# Programmer.net
KiCad netlist of a schematic drawn in Altium Designer
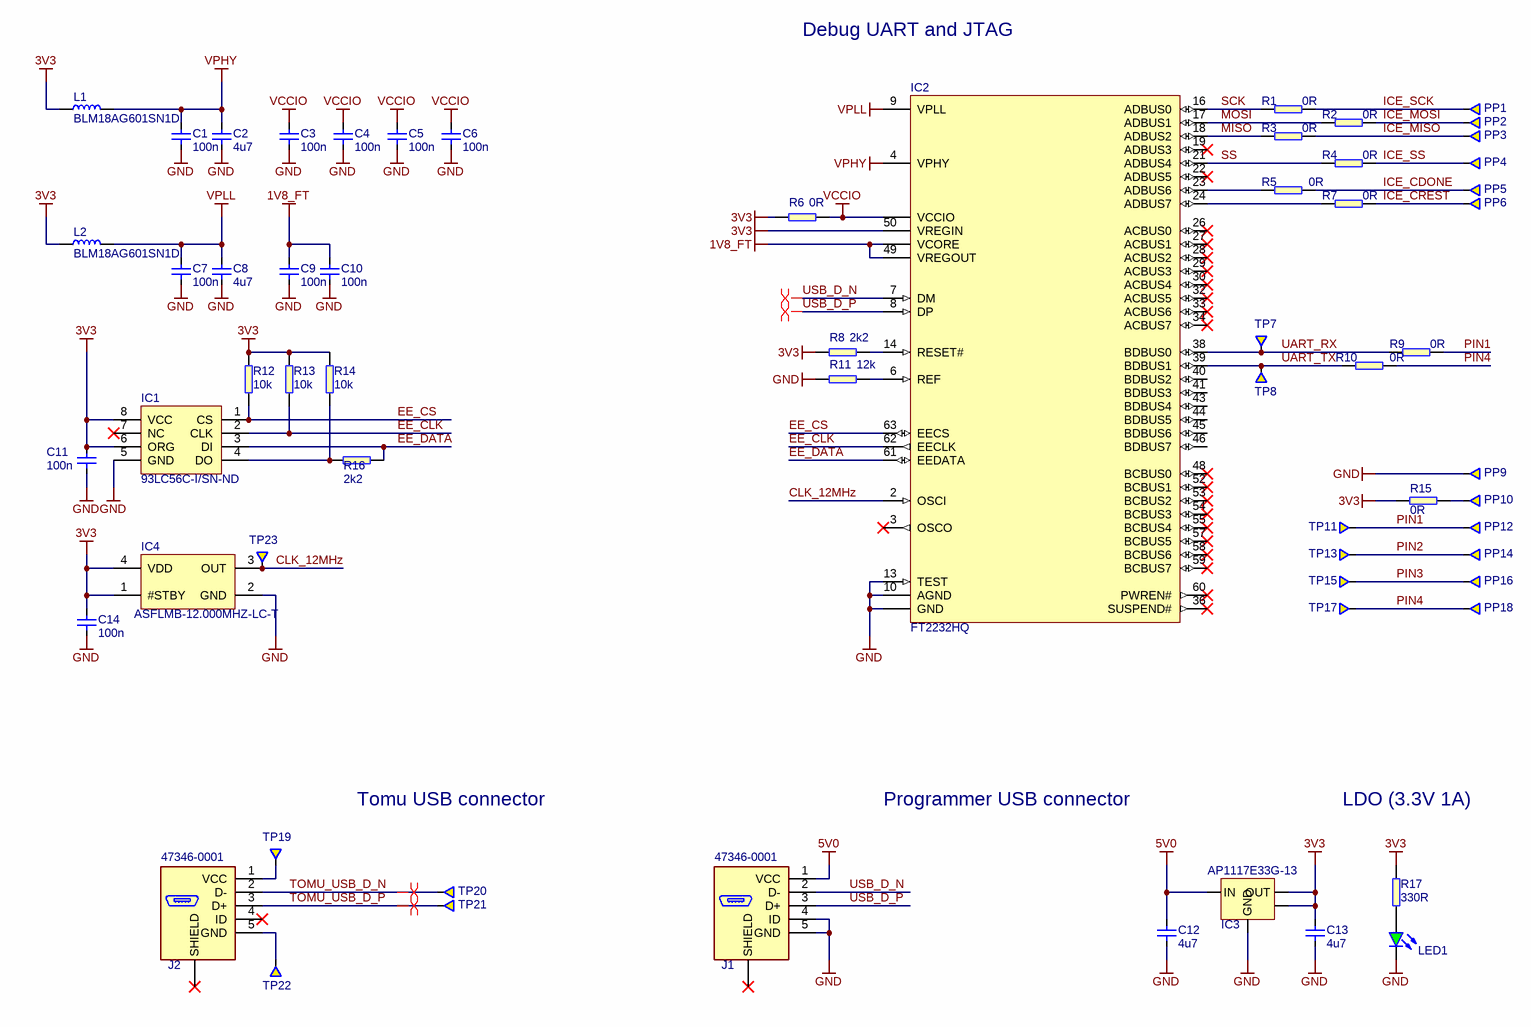
[diagram p0: Programmer.SchDoc]

(export (version "E")
  (design (tool "Eeschema 10.0.6"))
  (components
    (comp (ref "C1")
      (value "100n")
      (footprint "0402")
      (description "MLCC SMT Capacitor 100nF 0402")
      (fields (field (name "PARTNUMBER") "C_100n_0402") (field (name "MANUFACTURER") "AVX"))
      (libsource (lib "Tomu-ICE-Programmer-Rev.1.0") (part "C_100n_0402"))
    )
    (comp (ref "C2")
      (value "4u7")
      (footprint "0402")
      (description "MLCC SMT Capacitor 100nF 0402")
      (fields (field (name "PARTNUMBER") "C_4u7_0402") (field (name "MANUFACTURER") "TDK"))
      (libsource (lib "Tomu-ICE-Programmer-Rev.1.0") (part "C_4u7_0402"))
    )
    (comp (ref "C3")
      (value "100n")
      (footprint "0402")
      (description "MLCC SMT Capacitor 100nF 0402")
      (fields (field (name "PARTNUMBER") "C_100n_0402") (field (name "MANUFACTURER") "AVX"))
      (libsource (lib "Tomu-ICE-Programmer-Rev.1.0") (part "C_100n_0402"))
    )
    (comp (ref "C4")
      (value "100n")
      (footprint "0402")
      (description "MLCC SMT Capacitor 100nF 0402")
      (fields (field (name "PARTNUMBER") "C_100n_0402") (field (name "MANUFACTURER") "AVX"))
      (libsource (lib "Tomu-ICE-Programmer-Rev.1.0") (part "C_100n_0402"))
    )
    (comp (ref "C5")
      (value "100n")
      (footprint "0402")
      (description "MLCC SMT Capacitor 100nF 0402")
      (fields (field (name "PARTNUMBER") "C_100n_0402") (field (name "MANUFACTURER") "AVX"))
      (libsource (lib "Tomu-ICE-Programmer-Rev.1.0") (part "C_100n_0402"))
    )
    (comp (ref "C6")
      (value "100n")
      (footprint "0402")
      (description "MLCC SMT Capacitor 100nF 0402")
      (fields (field (name "PARTNUMBER") "C_100n_0402") (field (name "MANUFACTURER") "AVX"))
      (libsource (lib "Tomu-ICE-Programmer-Rev.1.0") (part "C_100n_0402"))
    )
    (comp (ref "C7")
      (value "100n")
      (footprint "0402")
      (description "MLCC SMT Capacitor 100nF 0402")
      (fields (field (name "PARTNUMBER") "C_100n_0402") (field (name "MANUFACTURER") "AVX"))
      (libsource (lib "Tomu-ICE-Programmer-Rev.1.0") (part "C_100n_0402"))
    )
    (comp (ref "C8")
      (value "4u7")
      (footprint "0402")
      (description "MLCC SMT Capacitor 100nF 0402")
      (fields (field (name "PARTNUMBER") "C_4u7_0402") (field (name "MANUFACTURER") "TDK"))
      (libsource (lib "Tomu-ICE-Programmer-Rev.1.0") (part "C_4u7_0402"))
    )
    (comp (ref "C9")
      (value "100n")
      (footprint "0402")
      (description "MLCC SMT Capacitor 100nF 0402")
      (fields (field (name "PARTNUMBER") "C_100n_0402") (field (name "MANUFACTURER") "AVX"))
      (libsource (lib "Tomu-ICE-Programmer-Rev.1.0") (part "C_100n_0402"))
    )
    (comp (ref "C10")
      (value "100n")
      (footprint "0402")
      (description "MLCC SMT Capacitor 100nF 0402")
      (fields (field (name "PARTNUMBER") "C_100n_0402") (field (name "MANUFACTURER") "AVX"))
      (libsource (lib "Tomu-ICE-Programmer-Rev.1.0") (part "C_100n_0402"))
    )
    (comp (ref "C11")
      (value "100n")
      (footprint "0402")
      (description "MLCC SMT Capacitor 100nF 0402")
      (fields (field (name "PARTNUMBER") "C_100n_0402") (field (name "MANUFACTURER") "AVX"))
      (libsource (lib "Tomu-ICE-Programmer-Rev.1.0") (part "C_100n_0402"))
    )
    (comp (ref "C12")
      (value "4u7")
      (footprint "0402")
      (description "MLCC SMT Capacitor 100nF 0402")
      (fields (field (name "PARTNUMBER") "C_4u7_0402") (field (name "MANUFACTURER") "TDK"))
      (libsource (lib "Tomu-ICE-Programmer-Rev.1.0") (part "C_4u7_0402"))
    )
    (comp (ref "C13")
      (value "4u7")
      (footprint "0402")
      (description "MLCC SMT Capacitor 100nF 0402")
      (fields (field (name "PARTNUMBER") "C_4u7_0402") (field (name "MANUFACTURER") "TDK"))
      (libsource (lib "Tomu-ICE-Programmer-Rev.1.0") (part "C_4u7_0402"))
    )
    (comp (ref "C14")
      (value "100n")
      (footprint "0402")
      (description "MLCC SMT Capacitor 100nF 0402")
      (fields (field (name "PARTNUMBER") "C_100n_0402") (field (name "MANUFACTURER") "AVX"))
      (libsource (lib "Tomu-ICE-Programmer-Rev.1.0") (part "C_100n_0402"))
    )
    (comp (ref "IC1")
      (value "93LC56C-I/SN-ND")
      (footprint "SOIC-8")
      (description "EEPROM SERIAL 1K, SMD, 93C46, SOIC8")
      (fields (field (name "PARTNUMBER") "93LC56C") (field (name "MANUFACTURER") "Microchip Technology"))
      (libsource (lib "Tomu-ICE-Programmer-Rev.1.0") (part "93LC56C"))
    )
    (comp (ref "IC2")
      (value "FT2232HQ")
      (footprint "FT2232HQ")
      (description "Dual USB-UART/FIFO")
      (fields (field (name "MANUFACTURER") "FTDI") (field (name "PARTNUMBER") "FT2232HQ"))
      (libsource (lib "Tomu-ICE-Programmer-Rev.1.0") (part "FT2232HL"))
    )
    (comp (ref "IC3")
      (value "AP1117E33G-13")
      (footprint "SOT223")
      (description "IC, LDO, REG, 3.3V, SOT223")
      (fields (field (name "MANUFACTURER") "DIODES INC."))
      (libsource (lib "Tomu-ICE-Programmer-Rev.1.0") (part "xx1117"))
    )
    (comp (ref "IC4")
      (value "ASFLMB-12.000MHZ-LC-T")
      (footprint "ASFLMB")
      (description "MEMS Oscillator, Ultra-miniature, 12 MHz, SMD, 5mm x 3.2mm, 50 ppm, 3.3 V")
      (fields (field (name "MANUFACTURER") "Abracon LLC"))
      (libsource (lib "Tomu-ICE-Programmer-Rev.1.0") (part "ASFLMB"))
    )
    (comp (ref "J1")
      (value "Molex 47346-0001")
      (footprint "CON-Molex-047346-0001")
      (description "USB - micro B Receptacle Connector 5 Position Surface Mount, Right Angle, Horizontal")
      (fields
        (field (name "PARTNUMBER") "CON-Molex-47346-0001")
        (field (name "MANUFACTURER") "Molex")
        (field (name "PARTSYMBOL") "47346-0001")
      )
      (libsource (lib "Tomu-ICE-Programmer-Rev.1.0") (part "Micro USB B"))
    )
    (comp (ref "J2")
      (value "Molex 47346-0001")
      (footprint "CON-Molex-047346-0001")
      (description "USB - micro B Receptacle Connector 5 Position Surface Mount, Right Angle, Horizontal")
      (fields
        (field (name "PARTNUMBER") "CON-Molex-47346-0001")
        (field (name "MANUFACTURER") "Molex")
        (field (name "PARTSYMBOL") "47346-0001")
      )
      (libsource (lib "Tomu-ICE-Programmer-Rev.1.0") (part "Micro USB B"))
    )
    (comp (ref "L1")
      (value "BLM18AG601SN1D")
      (footprint "0603")
      (description "Ferrite Bead, 600 ohm, 0603 [1608 Metric], BLM18A Series, 500 mA, 0.38 ohm, ? 25%")
      (fields (field (name "MANUFACTURER") "MURATA"))
      (libsource (lib "Tomu-ICE-Programmer-Rev.1.0") (part "Inductor SMT"))
    )
    (comp (ref "L2")
      (value "BLM18AG601SN1D")
      (footprint "0603")
      (description "Ferrite Bead, 600 ohm, 0603 [1608 Metric], BLM18A Series, 500 mA, 0.38 ohm, ? 25%")
      (fields (field (name "MANUFACTURER") "MURATA"))
      (libsource (lib "Tomu-ICE-Programmer-Rev.1.0") (part "Inductor SMT"))
    )
    (comp (ref "LED1")
      (value "KPT-1608SGC")
      (footprint "LED0603")
      (description "LED Green 0603 case")
      (fields (field (name "PARTNUMBER") "LED_G") (field (name "MANUFACTURER") "KINGBRIGHT"))
      (libsource (lib "Tomu-ICE-Programmer-Rev.1.0") (part "LED"))
    )
    (comp (ref "PP1")
      (value "~")
      (footprint "TP-R-1.5-THT")
      (description "Testpad, round, 1.8mm")
      (fields (field (name "PARTNUMBER") "P70-2300045R") (field (name "MANUFACTURER") "Harwin"))
      (libsource (lib "Tomu-ICE-Programmer-Rev.1.0") (part "Testpad_pin"))
    )
    (comp (ref "PP2")
      (value "~")
      (footprint "TP-R-1.5-THT")
      (description "Testpad, round, 1.8mm")
      (fields (field (name "PARTNUMBER") "P70-2300045R") (field (name "MANUFACTURER") "Harwin"))
      (libsource (lib "Tomu-ICE-Programmer-Rev.1.0") (part "Testpad_pin"))
    )
    (comp (ref "PP3")
      (value "~")
      (footprint "TP-R-1.5-THT")
      (description "Testpad, round, 1.8mm")
      (fields (field (name "PARTNUMBER") "P70-2300045R") (field (name "MANUFACTURER") "Harwin"))
      (libsource (lib "Tomu-ICE-Programmer-Rev.1.0") (part "Testpad_pin"))
    )
    (comp (ref "PP4")
      (value "~")
      (footprint "TP-R-1.5-THT")
      (description "Testpad, round, 1.8mm")
      (fields (field (name "PARTNUMBER") "P70-2300045R") (field (name "MANUFACTURER") "Harwin"))
      (libsource (lib "Tomu-ICE-Programmer-Rev.1.0") (part "Testpad_pin"))
    )
    (comp (ref "PP5")
      (value "~")
      (footprint "TP-R-1.5-THT")
      (description "Testpad, round, 1.8mm")
      (fields (field (name "PARTNUMBER") "P70-2300045R") (field (name "MANUFACTURER") "Harwin"))
      (libsource (lib "Tomu-ICE-Programmer-Rev.1.0") (part "Testpad_pin"))
    )
    (comp (ref "PP6")
      (value "~")
      (footprint "TP-R-1.5-THT")
      (description "Testpad, round, 1.8mm")
      (fields (field (name "PARTNUMBER") "P70-2300045R") (field (name "MANUFACTURER") "Harwin"))
      (libsource (lib "Tomu-ICE-Programmer-Rev.1.0") (part "Testpad_pin"))
    )
    (comp (ref "PP9")
      (value "~")
      (footprint "TP-R-1.5-THT")
      (description "Testpad, round, 1.8mm")
      (fields (field (name "PARTNUMBER") "P70-2300045R") (field (name "MANUFACTURER") "Harwin"))
      (libsource (lib "Tomu-ICE-Programmer-Rev.1.0") (part "Testpad_pin"))
    )
    (comp (ref "PP10")
      (value "~")
      (footprint "TP-R-1.5-THT")
      (description "Testpad, round, 1.8mm")
      (fields (field (name "PARTNUMBER") "P70-2300045R") (field (name "MANUFACTURER") "Harwin"))
      (libsource (lib "Tomu-ICE-Programmer-Rev.1.0") (part "Testpad_pin"))
    )
    (comp (ref "PP12")
      (value "~")
      (footprint "TP-R-1.5-THT")
      (description "Testpad, round, 1.8mm")
      (fields (field (name "PARTNUMBER") "P70-2300045R") (field (name "MANUFACTURER") "Harwin"))
      (libsource (lib "Tomu-ICE-Programmer-Rev.1.0") (part "Testpad_pin"))
    )
    (comp (ref "PP14")
      (value "~")
      (footprint "TP-R-1.5-THT")
      (description "Testpad, round, 1.8mm")
      (fields (field (name "PARTNUMBER") "P70-2300045R") (field (name "MANUFACTURER") "Harwin"))
      (libsource (lib "Tomu-ICE-Programmer-Rev.1.0") (part "Testpad_pin"))
    )
    (comp (ref "PP16")
      (value "~")
      (footprint "TP-R-1.5-THT")
      (description "Testpad, round, 1.8mm")
      (fields (field (name "PARTNUMBER") "P70-2300045R") (field (name "MANUFACTURER") "Harwin"))
      (libsource (lib "Tomu-ICE-Programmer-Rev.1.0") (part "Testpad_pin"))
    )
    (comp (ref "PP18")
      (value "~")
      (footprint "TP-R-1.5-THT")
      (description "Testpad, round, 1.8mm")
      (fields (field (name "PARTNUMBER") "P70-2300045R") (field (name "MANUFACTURER") "Harwin"))
      (libsource (lib "Tomu-ICE-Programmer-Rev.1.0") (part "Testpad_pin"))
    )
    (comp (ref "R1")
      (value "0R")
      (footprint "0402")
      (description "SMT Resistor 0402")
      (fields (field (name "PARTNUMBER") "R_0R_0402") (field (name "MANUFACTURER") "Vishay"))
      (libsource (lib "Tomu-ICE-Programmer-Rev.1.0") (part "R_0R_0402"))
    )
    (comp (ref "R2")
      (value "0R")
      (footprint "0402")
      (description "SMT Resistor 0402")
      (fields (field (name "PARTNUMBER") "R_0R_0402") (field (name "MANUFACTURER") "Vishay"))
      (libsource (lib "Tomu-ICE-Programmer-Rev.1.0") (part "R_0R_0402"))
    )
    (comp (ref "R3")
      (value "0R")
      (footprint "0402")
      (description "SMT Resistor 0402")
      (fields (field (name "PARTNUMBER") "R_0R_0402") (field (name "MANUFACTURER") "Vishay"))
      (libsource (lib "Tomu-ICE-Programmer-Rev.1.0") (part "R_0R_0402"))
    )
    (comp (ref "R4")
      (value "0R")
      (footprint "0402")
      (description "SMT Resistor 0402")
      (fields (field (name "PARTNUMBER") "R_0R_0402") (field (name "MANUFACTURER") "Vishay"))
      (libsource (lib "Tomu-ICE-Programmer-Rev.1.0") (part "R_0R_0402"))
    )
    (comp (ref "R5")
      (value "0R")
      (footprint "0402")
      (description "SMT Resistor 0402")
      (fields (field (name "PARTNUMBER") "R_0R_0402") (field (name "MANUFACTURER") "Vishay"))
      (libsource (lib "Tomu-ICE-Programmer-Rev.1.0") (part "R_0R_0402"))
    )
    (comp (ref "R6")
      (value "0R")
      (footprint "0402")
      (description "SMT Resistor 0402")
      (fields (field (name "PARTNUMBER") "R_0R_0402") (field (name "MANUFACTURER") "Vishay"))
      (libsource (lib "Tomu-ICE-Programmer-Rev.1.0") (part "R_0R_0402"))
    )
    (comp (ref "R7")
      (value "0R")
      (footprint "0402")
      (description "SMT Resistor 0402")
      (fields (field (name "PARTNUMBER") "R_0R_0402") (field (name "MANUFACTURER") "Vishay"))
      (libsource (lib "Tomu-ICE-Programmer-Rev.1.0") (part "R_0R_0402"))
    )
    (comp (ref "R8")
      (value "2k2")
      (footprint "0402")
      (description "SMT Resistor 0402")
      (fields (field (name "PARTNUMBER") "R_2k2_0402") (field (name "MANUFACTURER") "Vishay"))
      (libsource (lib "Tomu-ICE-Programmer-Rev.1.0") (part "R_2k2_0402"))
    )
    (comp (ref "R9")
      (value "0R")
      (footprint "0402")
      (description "SMT Resistor 0402")
      (fields (field (name "PARTNUMBER") "R_0R_0402") (field (name "MANUFACTURER") "Vishay"))
      (libsource (lib "Tomu-ICE-Programmer-Rev.1.0") (part "R_0R_0402"))
    )
    (comp (ref "R10")
      (value "0R")
      (footprint "0402")
      (description "SMT Resistor 0402")
      (fields (field (name "PARTNUMBER") "R_0R_0402") (field (name "MANUFACTURER") "Vishay"))
      (libsource (lib "Tomu-ICE-Programmer-Rev.1.0") (part "R_0R_0402"))
    )
    (comp (ref "R11")
      (value "12k")
      (footprint "0402")
      (description "SMT Resistor 0402")
      (fields (field (name "PARTNUMBER") "R_12k_0402") (field (name "MANUFACTURER") "Multicomp"))
      (libsource (lib "Tomu-ICE-Programmer-Rev.1.0") (part "R_12k_0402"))
    )
    (comp (ref "R12")
      (value "10k")
      (footprint "0402")
      (description "SMT Resistor 0402")
      (fields (field (name "PARTNUMBER") "R_10k_0402") (field (name "MANUFACTURER") "Vishay"))
      (libsource (lib "Tomu-ICE-Programmer-Rev.1.0") (part "R_10k_0402"))
    )
    (comp (ref "R13")
      (value "10k")
      (footprint "0402")
      (description "SMT Resistor 0402")
      (fields (field (name "PARTNUMBER") "R_10k_0402") (field (name "MANUFACTURER") "Vishay"))
      (libsource (lib "Tomu-ICE-Programmer-Rev.1.0") (part "R_10k_0402"))
    )
    (comp (ref "R14")
      (value "10k")
      (footprint "0402")
      (description "SMT Resistor 0402")
      (fields (field (name "PARTNUMBER") "R_10k_0402") (field (name "MANUFACTURER") "Vishay"))
      (libsource (lib "Tomu-ICE-Programmer-Rev.1.0") (part "R_10k_0402"))
    )
    (comp (ref "R15")
      (value "0R")
      (footprint "0402")
      (description "SMT Resistor 0402")
      (fields (field (name "PARTNUMBER") "R_0R_0402") (field (name "MANUFACTURER") "Vishay"))
      (libsource (lib "Tomu-ICE-Programmer-Rev.1.0") (part "R_0R_0402"))
    )
    (comp (ref "R16")
      (value "2k2")
      (footprint "0402")
      (description "SMT Resistor 0402")
      (fields (field (name "PARTNUMBER") "R_2k2_0402") (field (name "MANUFACTURER") "Vishay"))
      (libsource (lib "Tomu-ICE-Programmer-Rev.1.0") (part "R_2k2_0402"))
    )
    (comp (ref "R17")
      (value "330R")
      (footprint "0402")
      (description "SMT Resistor 0402")
      (fields (field (name "PARTNUMBER") "R_330R_0402") (field (name "MANUFACTURER") "Multicomp"))
      (libsource (lib "Tomu-ICE-Programmer-Rev.1.0") (part "R_330R_0402"))
    )
    (comp (ref "TP7")
      (value "Testpad")
      (footprint "TP-R-1.5")
      (description "Testpad, round, 1.5mm")
      (fields (field (name "PARTNUMBER") "TP-R-1.5"))
      (libsource (lib "Tomu-ICE-Programmer-Rev.1.0") (part "Testpad"))
    )
    (comp (ref "TP8")
      (value "Testpad")
      (footprint "TP-R-1.5")
      (description "Testpad, round, 1.5mm")
      (fields (field (name "PARTNUMBER") "TP-R-1.5"))
      (libsource (lib "Tomu-ICE-Programmer-Rev.1.0") (part "Testpad"))
    )
    (comp (ref "TP11")
      (value "Testpad")
      (footprint "TP-R-1.5")
      (description "Testpad, round, 1.5mm")
      (fields (field (name "PARTNUMBER") "TP-R-1.5"))
      (libsource (lib "Tomu-ICE-Programmer-Rev.1.0") (part "Testpad"))
    )
    (comp (ref "TP13")
      (value "Testpad")
      (footprint "TP-R-1.5")
      (description "Testpad, round, 1.5mm")
      (fields (field (name "PARTNUMBER") "TP-R-1.5"))
      (libsource (lib "Tomu-ICE-Programmer-Rev.1.0") (part "Testpad"))
    )
    (comp (ref "TP15")
      (value "Testpad")
      (footprint "TP-R-1.5")
      (description "Testpad, round, 1.5mm")
      (fields (field (name "PARTNUMBER") "TP-R-1.5"))
      (libsource (lib "Tomu-ICE-Programmer-Rev.1.0") (part "Testpad"))
    )
    (comp (ref "TP17")
      (value "Testpad")
      (footprint "TP-R-1.5")
      (description "Testpad, round, 1.5mm")
      (fields (field (name "PARTNUMBER") "TP-R-1.5"))
      (libsource (lib "Tomu-ICE-Programmer-Rev.1.0") (part "Testpad"))
    )
    (comp (ref "TP19")
      (value "Testpad")
      (footprint "TP-R-1.5")
      (description "Testpad, round, 1.5mm")
      (fields (field (name "PARTNUMBER") "TP-R-1.5"))
      (libsource (lib "Tomu-ICE-Programmer-Rev.1.0") (part "Testpad"))
    )
    (comp (ref "TP20")
      (value "Testpad")
      (footprint "TP-R-1.5")
      (description "Testpad, round, 1.5mm")
      (fields (field (name "PARTNUMBER") "TP-R-1.5"))
      (libsource (lib "Tomu-ICE-Programmer-Rev.1.0") (part "Testpad"))
    )
    (comp (ref "TP21")
      (value "Testpad")
      (footprint "TP-R-1.5")
      (description "Testpad, round, 1.5mm")
      (fields (field (name "PARTNUMBER") "TP-R-1.5"))
      (libsource (lib "Tomu-ICE-Programmer-Rev.1.0") (part "Testpad"))
    )
    (comp (ref "TP22")
      (value "Testpad")
      (footprint "TP-R-1.5")
      (description "Testpad, round, 1.5mm")
      (fields (field (name "PARTNUMBER") "TP-R-1.5"))
      (libsource (lib "Tomu-ICE-Programmer-Rev.1.0") (part "Testpad"))
    )
    (comp (ref "TP23")
      (value "Testpad")
      (footprint "TP-R-1.5")
      (description "Testpad, round, 1.5mm")
      (fields (field (name "PARTNUMBER") "TP-R-1.5"))
      (libsource (lib "Tomu-ICE-Programmer-Rev.1.0") (part "Testpad"))
    )
  )
  (nets
    (net (code "1") (name "/CLK_12MHz") (class "Default")
      (node (ref "IC2") (pin "2") (pinfunction "OSCI_2") (pintype "input"))
      (node (ref "IC4") (pin "3") (pinfunction "OUT_3") (pintype "passive"))
      (node (ref "TP23") (pin "1") (pintype "passive"))
    )
    (net (code "2") (name "/EE_CLK") (class "Default")
      (node (ref "IC1") (pin "2") (pinfunction "CLK_2") (pintype "passive"))
      (node (ref "IC2") (pin "62") (pinfunction "EECLK_62") (pintype "output"))
      (node (ref "R13") (pin "1") (pintype "passive"))
    )
    (net (code "3") (name "/EE_CS") (class "Default")
      (node (ref "IC1") (pin "1") (pinfunction "CS_1") (pintype "passive"))
      (node (ref "IC2") (pin "63") (pinfunction "EECS_63") (pintype "bidirectional"))
      (node (ref "R12") (pin "1") (pintype "passive"))
    )
    (net (code "4") (name "/EE_DATA") (class "Default")
      (node (ref "IC1") (pin "3") (pinfunction "DI_3") (pintype "passive"))
      (node (ref "IC2") (pin "61") (pinfunction "EEDATA_61") (pintype "bidirectional"))
      (node (ref "R16") (pin "2") (pintype "passive"))
    )
    (net (code "5") (name "/ICE_CDONE") (class "Default")
      (node (ref "PP5") (pin "1") (pintype "passive"))
      (node (ref "R5") (pin "2") (pintype "passive"))
    )
    (net (code "6") (name "/ICE_CREST") (class "Default")
      (node (ref "PP6") (pin "1") (pintype "passive"))
      (node (ref "R7") (pin "2") (pintype "passive"))
    )
    (net (code "7") (name "/ICE_MISO") (class "Default")
      (node (ref "PP3") (pin "1") (pintype "passive"))
      (node (ref "R3") (pin "2") (pintype "passive"))
    )
    (net (code "8") (name "/ICE_MOSI") (class "Default")
      (node (ref "PP2") (pin "1") (pintype "passive"))
      (node (ref "R2") (pin "2") (pintype "passive"))
    )
    (net (code "9") (name "/ICE_SCK") (class "Default")
      (node (ref "PP1") (pin "1") (pintype "passive"))
      (node (ref "R1") (pin "2") (pintype "passive"))
    )
    (net (code "10") (name "/ICE_SS") (class "Default")
      (node (ref "PP4") (pin "1") (pintype "passive"))
      (node (ref "R4") (pin "2") (pintype "passive"))
    )
    (net (code "11") (name "/MISO") (class "Default")
      (node (ref "IC2") (pin "18") (pinfunction "ADBUS2_18") (pintype "bidirectional"))
      (node (ref "R3") (pin "1") (pintype "passive"))
    )
    (net (code "12") (name "/MOSI") (class "Default")
      (node (ref "IC2") (pin "17") (pinfunction "ADBUS1_17") (pintype "bidirectional"))
      (node (ref "R2") (pin "1") (pintype "passive"))
    )
    (net (code "13") (name "/PIN1") (class "Default")
      (node (ref "PP12") (pin "1") (pintype "passive"))
      (node (ref "R9") (pin "2") (pintype "passive"))
      (node (ref "TP11") (pin "1") (pintype "passive"))
    )
    (net (code "14") (name "/PIN2") (class "Default")
      (node (ref "PP14") (pin "1") (pintype "passive"))
      (node (ref "TP13") (pin "1") (pintype "passive"))
    )
    (net (code "15") (name "/PIN3") (class "Default")
      (node (ref "PP16") (pin "1") (pintype "passive"))
      (node (ref "TP15") (pin "1") (pintype "passive"))
    )
    (net (code "16") (name "/PIN4") (class "Default")
      (node (ref "PP18") (pin "1") (pintype "passive"))
      (node (ref "R10") (pin "2") (pintype "passive"))
      (node (ref "TP17") (pin "1") (pintype "passive"))
    )
    (net (code "17") (name "/SCK") (class "Default")
      (node (ref "IC2") (pin "16") (pinfunction "ADBUS0_16") (pintype "bidirectional"))
      (node (ref "R1") (pin "1") (pintype "passive"))
    )
    (net (code "18") (name "/SS") (class "Default")
      (node (ref "IC2") (pin "21") (pinfunction "ADBUS4_21") (pintype "bidirectional"))
      (node (ref "R4") (pin "1") (pintype "passive"))
    )
    (net (code "19") (name "/TOMU_USB_D_N") (class "Default")
      (node (ref "J2") (pin "2") (pinfunction "D-_2") (pintype "passive"))
      (node (ref "TP20") (pin "1") (pintype "passive"))
    )
    (net (code "20") (name "/TOMU_USB_D_P") (class "Default")
      (node (ref "J2") (pin "3") (pinfunction "D+_3") (pintype "passive"))
      (node (ref "TP21") (pin "1") (pintype "passive"))
    )
    (net (code "21") (name "/UART_RX") (class "Default")
      (node (ref "IC2") (pin "38") (pinfunction "BDBUS0_38") (pintype "bidirectional"))
      (node (ref "R9") (pin "1") (pintype "passive"))
      (node (ref "TP7") (pin "1") (pintype "passive"))
    )
    (net (code "22") (name "/UART_TX") (class "Default")
      (node (ref "IC2") (pin "39") (pinfunction "BDBUS1_39") (pintype "bidirectional"))
      (node (ref "R10") (pin "1") (pintype "passive"))
      (node (ref "TP8") (pin "1") (pintype "passive"))
    )
    (net (code "23") (name "/USB_D_N") (class "Default")
      (node (ref "IC2") (pin "7") (pinfunction "DM_7") (pintype "input"))
      (node (ref "J1") (pin "2") (pinfunction "D-_2") (pintype "passive"))
    )
    (net (code "24") (name "/USB_D_P") (class "Default")
      (node (ref "IC2") (pin "8") (pinfunction "DP_8") (pintype "input"))
      (node (ref "J1") (pin "3") (pinfunction "D+_3") (pintype "passive"))
    )
    (net (code "25") (name "1V8_FT") (class "Default")
      (node (ref "C10") (pin "2") (pinfunction "2_2") (pintype "passive"))
      (node (ref "C9") (pin "2") (pinfunction "2_2") (pintype "passive"))
      (node (ref "IC2") (pin "49") (pinfunction "VREGOUT_49") (pintype "power_in"))
      (node (ref "IC2") (pin "VCORE") (pinfunction "VCORE_VCORE") (pintype "power_in"))
    )
    (net (code "26") (name "3V3") (class "Default")
      (node (ref "C11") (pin "2") (pinfunction "2_2") (pintype "passive"))
      (node (ref "C13") (pin "2") (pinfunction "2_2") (pintype "passive"))
      (node (ref "C14") (pin "2") (pinfunction "2_2") (pintype "passive"))
      (node (ref "IC1") (pin "6") (pinfunction "ORG_6") (pintype "passive"))
      (node (ref "IC1") (pin "8") (pinfunction "VCC_8") (pintype "passive"))
      (node (ref "IC2") (pin "50") (pinfunction "VREGIN_50") (pintype "power_in"))
      (node (ref "IC3") (pin "2") (pinfunction "OUT_2") (pintype "passive"))
      (node (ref "IC3") (pin "4") (pinfunction "OUT_4") (pintype "passive"))
      (node (ref "IC4") (pin "1") (pinfunction "#STBY_1") (pintype "passive"))
      (node (ref "IC4") (pin "4") (pinfunction "VDD_4") (pintype "passive"))
      (node (ref "L1") (pin "1") (pintype "passive"))
      (node (ref "L2") (pin "1") (pintype "passive"))
      (node (ref "R12") (pin "2") (pintype "passive"))
      (node (ref "R13") (pin "2") (pintype "passive"))
      (node (ref "R14") (pin "2") (pintype "passive"))
      (node (ref "R15") (pin "1") (pintype "passive"))
      (node (ref "R17") (pin "2") (pintype "passive"))
      (node (ref "R6") (pin "1") (pintype "passive"))
      (node (ref "R8") (pin "1") (pintype "passive"))
    )
    (net (code "27") (name "5V0") (class "Default")
      (node (ref "C12") (pin "2") (pinfunction "2_2") (pintype "passive"))
      (node (ref "IC3") (pin "3") (pinfunction "IN_3") (pintype "power_in"))
      (node (ref "J1") (pin "1") (pinfunction "VCC_1") (pintype "power_in"))
    )
    (net (code "28") (name "GND") (class "Default")
      (node (ref "C1") (pin "1") (pinfunction "1_1") (pintype "passive"))
      (node (ref "C10") (pin "1") (pinfunction "1_1") (pintype "passive"))
      (node (ref "C11") (pin "1") (pinfunction "1_1") (pintype "passive"))
      (node (ref "C12") (pin "1") (pinfunction "1_1") (pintype "passive"))
      (node (ref "C13") (pin "1") (pinfunction "1_1") (pintype "passive"))
      (node (ref "C14") (pin "1") (pinfunction "1_1") (pintype "passive"))
      (node (ref "C2") (pin "1") (pinfunction "1_1") (pintype "passive"))
      (node (ref "C3") (pin "1") (pinfunction "1_1") (pintype "passive"))
      (node (ref "C4") (pin "1") (pinfunction "1_1") (pintype "passive"))
      (node (ref "C5") (pin "1") (pinfunction "1_1") (pintype "passive"))
      (node (ref "C6") (pin "1") (pinfunction "1_1") (pintype "passive"))
      (node (ref "C7") (pin "1") (pinfunction "1_1") (pintype "passive"))
      (node (ref "C8") (pin "1") (pinfunction "1_1") (pintype "passive"))
      (node (ref "C9") (pin "1") (pinfunction "1_1") (pintype "passive"))
      (node (ref "IC1") (pin "5") (pinfunction "GND_5") (pintype "passive"))
      (node (ref "IC2") (pin "10") (pinfunction "AGND_10") (pintype "power_in"))
      (node (ref "IC2") (pin "13") (pinfunction "TEST_13") (pintype "input"))
      (node (ref "IC2") (pin "GND") (pinfunction "GND_GND") (pintype "power_in"))
      (node (ref "IC3") (pin "1") (pinfunction "GND_1") (pintype "power_in"))
      (node (ref "IC4") (pin "2") (pinfunction "GND_2") (pintype "passive"))
      (node (ref "J1") (pin "4") (pinfunction "ID_4") (pintype "passive"))
      (node (ref "J1") (pin "5") (pinfunction "GND_5") (pintype "power_in"))
      (node (ref "LED1") (pin "K") (pinfunction "K_K") (pintype "passive"))
      (node (ref "PP9") (pin "1") (pintype "passive"))
      (node (ref "R11") (pin "1") (pintype "passive"))
    )
    (net (code "29") (name "Net-(IC1-DO)") (class "Default")
      (node (ref "IC1") (pin "4") (pinfunction "DO_4") (pintype "passive"))
      (node (ref "R14") (pin "1") (pintype "passive"))
      (node (ref "R16") (pin "1") (pintype "passive"))
    )
    (net (code "30") (name "Net-(IC2-ADBUS6)") (class "Default")
      (node (ref "IC2") (pin "23") (pinfunction "ADBUS6_23") (pintype "bidirectional"))
      (node (ref "R5") (pin "1") (pintype "passive"))
    )
    (net (code "31") (name "Net-(IC2-ADBUS7)") (class "Default")
      (node (ref "IC2") (pin "24") (pinfunction "ADBUS7_24") (pintype "bidirectional"))
      (node (ref "R7") (pin "1") (pintype "passive"))
    )
    (net (code "32") (name "Net-(IC2-REF)") (class "Default")
      (node (ref "IC2") (pin "6") (pinfunction "REF_6") (pintype "input"))
      (node (ref "R11") (pin "2") (pintype "passive"))
    )
    (net (code "33") (name "Net-(IC2-RESET#)") (class "Default")
      (node (ref "IC2") (pin "14") (pinfunction "RESET#_14") (pintype "input"))
      (node (ref "R8") (pin "2") (pintype "passive"))
    )
    (net (code "34") (name "Net-(J2-GND)") (class "Default")
      (node (ref "J2") (pin "5") (pinfunction "GND_5") (pintype "power_in"))
      (node (ref "TP22") (pin "1") (pintype "passive"))
    )
    (net (code "35") (name "Net-(J2-VCC)") (class "Default")
      (node (ref "J2") (pin "1") (pinfunction "VCC_1") (pintype "power_in"))
      (node (ref "TP19") (pin "1") (pintype "passive"))
    )
    (net (code "36") (name "Net-(LED1-PadA)") (class "Default")
      (node (ref "LED1") (pin "A") (pinfunction "A_A") (pintype "passive"))
      (node (ref "R17") (pin "1") (pintype "passive"))
    )
    (net (code "37") (name "Net-(PP10-Pad1)") (class "Default")
      (node (ref "PP10") (pin "1") (pintype "passive"))
      (node (ref "R15") (pin "2") (pintype "passive"))
    )
    (net (code "38") (name "VCCIO") (class "Default")
      (node (ref "C3") (pin "2") (pinfunction "2_2") (pintype "passive"))
      (node (ref "C4") (pin "2") (pinfunction "2_2") (pintype "passive"))
      (node (ref "C5") (pin "2") (pinfunction "2_2") (pintype "passive"))
      (node (ref "C6") (pin "2") (pinfunction "2_2") (pintype "passive"))
      (node (ref "IC2") (pin "VCCIO") (pinfunction "VCCIO_VCCIO") (pintype "power_in"))
      (node (ref "R6") (pin "2") (pintype "passive"))
    )
    (net (code "39") (name "VPHY") (class "Default")
      (node (ref "C1") (pin "2") (pinfunction "2_2") (pintype "passive"))
      (node (ref "C2") (pin "2") (pinfunction "2_2") (pintype "passive"))
      (node (ref "IC2") (pin "4") (pinfunction "VPHY_4") (pintype "power_in"))
      (node (ref "L1") (pin "2") (pintype "passive"))
    )
    (net (code "40") (name "VPLL") (class "Default")
      (node (ref "C7") (pin "2") (pinfunction "2_2") (pintype "passive"))
      (node (ref "C8") (pin "2") (pinfunction "2_2") (pintype "passive"))
      (node (ref "IC2") (pin "9") (pinfunction "VPLL_9") (pintype "power_in"))
      (node (ref "L2") (pin "2") (pintype "passive"))
    )
    (net (code "41") (name "unconnected-(IC1-NC-Pad7)") (class "Default")
      (node (ref "IC1") (pin "7") (pinfunction "NC_7") (pintype "passive+no_connect"))
    )
    (net (code "42") (name "unconnected-(IC2-ACBUS0-Pad26)") (class "Default")
      (node (ref "IC2") (pin "26") (pinfunction "ACBUS0_26") (pintype "bidirectional+no_connect"))
    )
    (net (code "43") (name "unconnected-(IC2-ACBUS1-Pad27)") (class "Default")
      (node (ref "IC2") (pin "27") (pinfunction "ACBUS1_27") (pintype "bidirectional+no_connect"))
    )
    (net (code "44") (name "unconnected-(IC2-ACBUS2-Pad28)") (class "Default")
      (node (ref "IC2") (pin "28") (pinfunction "ACBUS2_28") (pintype "bidirectional+no_connect"))
    )
    (net (code "45") (name "unconnected-(IC2-ACBUS3-Pad29)") (class "Default")
      (node (ref "IC2") (pin "29") (pinfunction "ACBUS3_29") (pintype "bidirectional+no_connect"))
    )
    (net (code "46") (name "unconnected-(IC2-ACBUS4-Pad30)") (class "Default")
      (node (ref "IC2") (pin "30") (pinfunction "ACBUS4_30") (pintype "bidirectional+no_connect"))
    )
    (net (code "47") (name "unconnected-(IC2-ACBUS5-Pad32)") (class "Default")
      (node (ref "IC2") (pin "32") (pinfunction "ACBUS5_32") (pintype "bidirectional+no_connect"))
    )
    (net (code "48") (name "unconnected-(IC2-ACBUS6-Pad33)") (class "Default")
      (node (ref "IC2") (pin "33") (pinfunction "ACBUS6_33") (pintype "bidirectional+no_connect"))
    )
    (net (code "49") (name "unconnected-(IC2-ACBUS7-Pad34)") (class "Default")
      (node (ref "IC2") (pin "34") (pinfunction "ACBUS7_34") (pintype "bidirectional+no_connect"))
    )
    (net (code "50") (name "unconnected-(IC2-ADBUS3-Pad19)") (class "Default")
      (node (ref "IC2") (pin "19") (pinfunction "ADBUS3_19") (pintype "bidirectional+no_connect"))
    )
    (net (code "51") (name "unconnected-(IC2-ADBUS5-Pad22)") (class "Default")
      (node (ref "IC2") (pin "22") (pinfunction "ADBUS5_22") (pintype "bidirectional+no_connect"))
    )
    (net (code "52") (name "unconnected-(IC2-BCBUS0-Pad48)") (class "Default")
      (node (ref "IC2") (pin "48") (pinfunction "BCBUS0_48") (pintype "bidirectional+no_connect"))
    )
    (net (code "53") (name "unconnected-(IC2-BCBUS1-Pad52)") (class "Default")
      (node (ref "IC2") (pin "52") (pinfunction "BCBUS1_52") (pintype "bidirectional+no_connect"))
    )
    (net (code "54") (name "unconnected-(IC2-BCBUS2-Pad53)") (class "Default")
      (node (ref "IC2") (pin "53") (pinfunction "BCBUS2_53") (pintype "bidirectional+no_connect"))
    )
    (net (code "55") (name "unconnected-(IC2-BCBUS3-Pad54)") (class "Default")
      (node (ref "IC2") (pin "54") (pinfunction "BCBUS3_54") (pintype "bidirectional+no_connect"))
    )
    (net (code "56") (name "unconnected-(IC2-BCBUS4-Pad55)") (class "Default")
      (node (ref "IC2") (pin "55") (pinfunction "BCBUS4_55") (pintype "bidirectional+no_connect"))
    )
    (net (code "57") (name "unconnected-(IC2-BCBUS5-Pad57)") (class "Default")
      (node (ref "IC2") (pin "57") (pinfunction "BCBUS5_57") (pintype "bidirectional+no_connect"))
    )
    (net (code "58") (name "unconnected-(IC2-BCBUS6-Pad58)") (class "Default")
      (node (ref "IC2") (pin "58") (pinfunction "BCBUS6_58") (pintype "bidirectional+no_connect"))
    )
    (net (code "59") (name "unconnected-(IC2-BCBUS7-Pad59)") (class "Default")
      (node (ref "IC2") (pin "59") (pinfunction "BCBUS7_59") (pintype "bidirectional+no_connect"))
    )
    (net (code "60") (name "unconnected-(IC2-BDBUS2-Pad40)") (class "Default")
      (node (ref "IC2") (pin "40") (pinfunction "BDBUS2_40") (pintype "bidirectional"))
    )
    (net (code "61") (name "unconnected-(IC2-BDBUS3-Pad41)") (class "Default")
      (node (ref "IC2") (pin "41") (pinfunction "BDBUS3_41") (pintype "bidirectional"))
    )
    (net (code "62") (name "unconnected-(IC2-BDBUS4-Pad43)") (class "Default")
      (node (ref "IC2") (pin "43") (pinfunction "BDBUS4_43") (pintype "bidirectional"))
    )
    (net (code "63") (name "unconnected-(IC2-BDBUS5-Pad44)") (class "Default")
      (node (ref "IC2") (pin "44") (pinfunction "BDBUS5_44") (pintype "bidirectional"))
    )
    (net (code "64") (name "unconnected-(IC2-BDBUS6-Pad45)") (class "Default")
      (node (ref "IC2") (pin "45") (pinfunction "BDBUS6_45") (pintype "bidirectional"))
    )
    (net (code "65") (name "unconnected-(IC2-BDBUS7-Pad46)") (class "Default")
      (node (ref "IC2") (pin "46") (pinfunction "BDBUS7_46") (pintype "bidirectional"))
    )
    (net (code "66") (name "unconnected-(IC2-OSCO-Pad3)") (class "Default")
      (node (ref "IC2") (pin "3") (pinfunction "OSCO_3") (pintype "output+no_connect"))
    )
    (net (code "67") (name "unconnected-(IC2-PWREN#-Pad60)") (class "Default")
      (node (ref "IC2") (pin "60") (pinfunction "PWREN#_60") (pintype "output+no_connect"))
    )
    (net (code "68") (name "unconnected-(IC2-SUSPEND#-Pad36)") (class "Default")
      (node (ref "IC2") (pin "36") (pinfunction "SUSPEND#_36") (pintype "output+no_connect"))
    )
    (net (code "69") (name "unconnected-(J1-SHIELD-PadS)") (class "Default")
      (node (ref "J1") (pin "S") (pinfunction "SHIELD_S") (pintype "passive+no_connect"))
    )
    (net (code "70") (name "unconnected-(J2-ID-Pad4)") (class "Default")
      (node (ref "J2") (pin "4") (pinfunction "ID_4") (pintype "passive+no_connect"))
    )
    (net (code "71") (name "unconnected-(J2-SHIELD-PadS)") (class "Default")
      (node (ref "J2") (pin "S") (pinfunction "SHIELD_S") (pintype "passive+no_connect"))
    )
  )
)
